# DiscoCarrier.net
KiCad netlist of a schematic drawn in Altium Designer
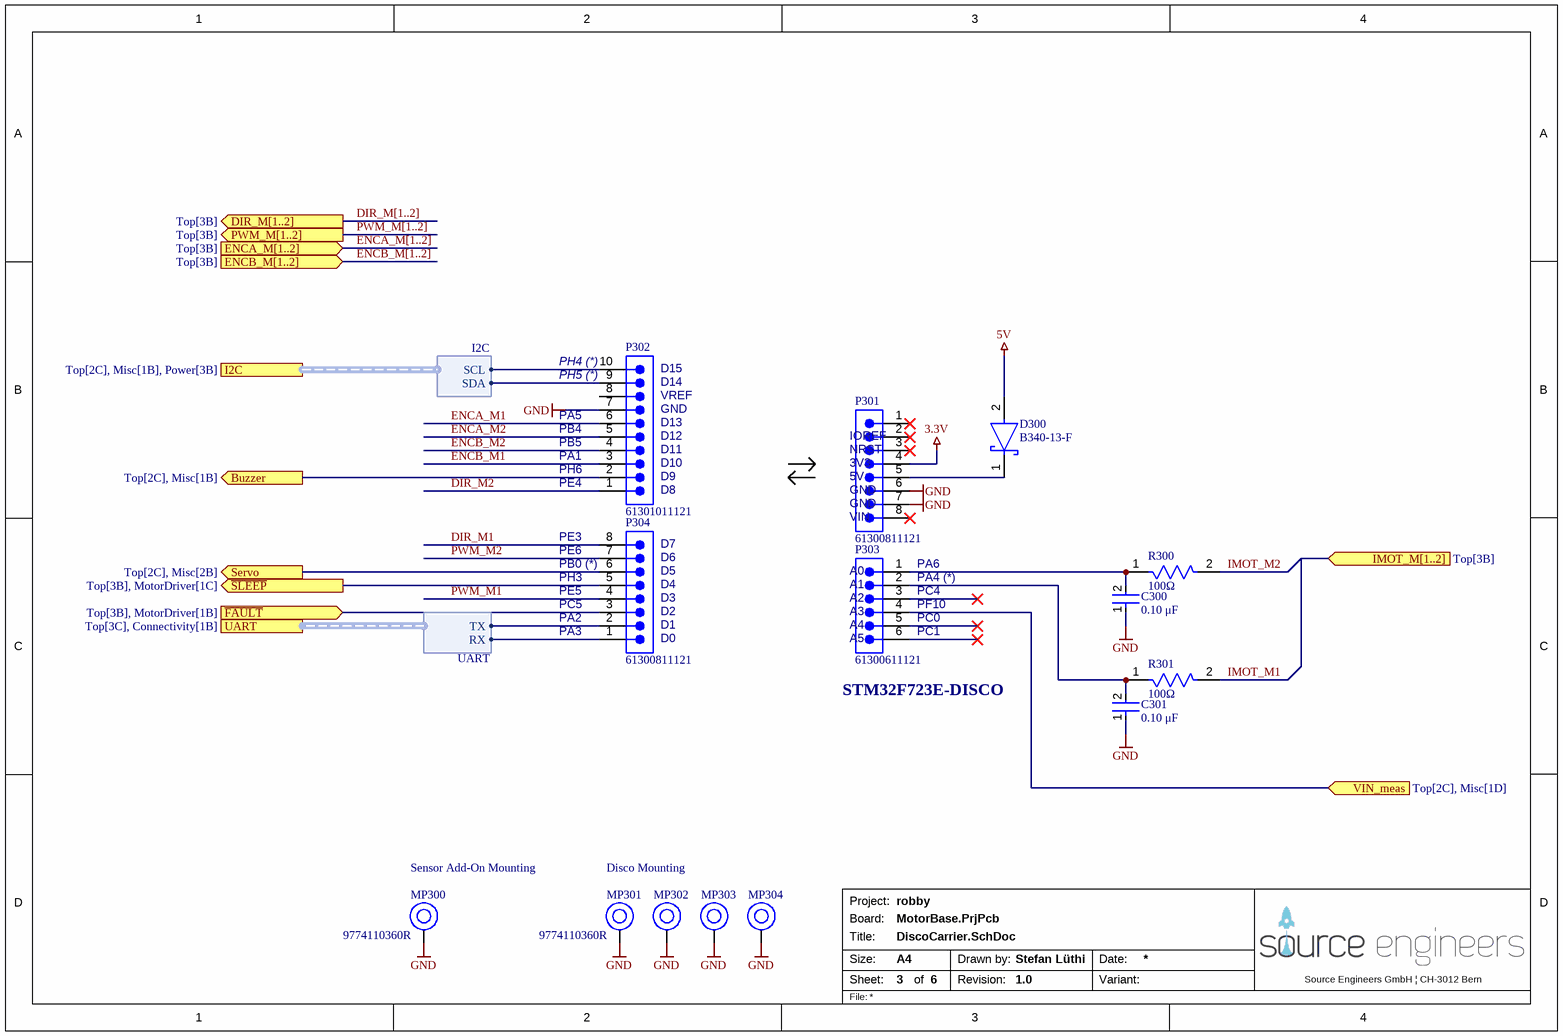
[diagram p0: DiscoCarrier.SchDoc]

(export (version "E")
  (design (tool "Eeschema 10.0.6"))
  (components
    (comp (ref "C300")
      (value "0.10 μF")
      (footprint "FP-C0603C-CF-MFG")
      (description "CAP CER 0.1UF 50V 20% X7R 0603")
      (fields
        (field (name "MANUFACTURER PART NUMBER") "C0603C104M5RACTU")
        (field (name "MANUFACTURER") "KEMET")
      )
      (libsource (lib "Altium Content Vault") (part "b4654b650e69147ec39a6b967a45e02"))
    )
    (comp (ref "C301")
      (value "0.10 μF")
      (footprint "FP-C0603C-CF-MFG")
      (description "CAP CER 0.1UF 50V 20% X7R 0603")
      (fields
        (field (name "MANUFACTURER PART NUMBER") "C0603C104M5RACTU")
        (field (name "MANUFACTURER") "KEMET")
      )
      (libsource (lib "Altium Content Vault") (part "b4654b650e69147ec39a6b967a45e02"))
    )
    (comp (ref "D300")
      (value "B340-13-F")
      (footprint "FP-SMC-MFG")
      (description "DIODE SCHOTTKY 40V 3A SMC")
      (fields
        (field (name "MANUFACTURER") "Diodes Inc.")
        (field (name "OCTOPART") "https://octopart.com/b340-13-f-diodes+inc.-325814")
      )
      (libsource (lib "Altium Content Vault") (part "1d6ec82d83fb6aee721767c19dac4b9"))
    )
    (comp (ref "MP300")
      (value "9774110360R")
      (footprint "9774110360")
      (description "9774110360R Spacer Material: Steel, Tin-Plated Mounting: SMT Series: WA-SMSI Thread D: M3")
      (libsource (lib "Altium Content Vault") (part "Spacer"))
    )
    (comp (ref "MP301")
      (value "9774110360R")
      (footprint "9774110360")
      (description "9774110360R Spacer Material: Steel, Tin-Plated Mounting: SMT Series: WA-SMSI Thread D: M3")
      (libsource (lib "Altium Content Vault") (part "Spacer"))
    )
    (comp (ref "MP302")
      (value "9774110360R")
      (footprint "9774110360")
      (description "9774110360R Spacer Material: Steel, Tin-Plated Mounting: SMT Series: WA-SMSI Thread D: M3")
      (libsource (lib "Altium Content Vault") (part "Spacer"))
    )
    (comp (ref "MP303")
      (value "9774110360R")
      (footprint "9774110360")
      (description "9774110360R Spacer Material: Steel, Tin-Plated Mounting: SMT Series: WA-SMSI Thread D: M3")
      (libsource (lib "Altium Content Vault") (part "Spacer"))
    )
    (comp (ref "MP304")
      (value "9774110360R")
      (footprint "9774110360")
      (description "9774110360R Spacer Material: Steel, Tin-Plated Mounting: SMT Series: WA-SMSI Thread D: M3")
      (libsource (lib "Altium Content Vault") (part "Spacer"))
    )
    (comp (ref "P301")
      (value "61300811121")
      (footprint "61300811121")
      (libsource (lib "Altium Content Vault") (part "Header_Male_1R_08P"))
    )
    (comp (ref "P302")
      (value "61301011121")
      (footprint "61301011121")
      (libsource (lib "Altium Content Vault") (part "Header_Male_1R_10P"))
    )
    (comp (ref "P303")
      (value "61300611121")
      (footprint "61300611121")
      (libsource (lib "Altium Content Vault") (part "Header_Male_1R_06P"))
    )
    (comp (ref "P304")
      (value "61300811121")
      (footprint "61300811121")
      (libsource (lib "Altium Content Vault") (part "Header_Male_1R_08P"))
    )
    (comp (ref "R300")
      (value "RT0603FRE07100RL")
      (footprint "FP-RT0603-MFG")
      (description "RES SMD 100 OHM 1% 1/10W 0603")
      (fields
        (field (name "MANUFACTURER") "Yageo")
        (field (name "RESISTANCE") "100Ω")
        (field (name "TOLERANCE") "0.01")
      )
      (libsource (lib "Altium Content Vault") (part "1029c3af85768c4190bb7ad29bc67b5"))
    )
    (comp (ref "R301")
      (value "RT0603FRE07100RL")
      (footprint "FP-RT0603-MFG")
      (description "RES SMD 100 OHM 1% 1/10W 0603")
      (fields
        (field (name "MANUFACTURER") "Yageo")
        (field (name "RESISTANCE") "100Ω")
        (field (name "TOLERANCE") "0.01")
      )
      (libsource (lib "Altium Content Vault") (part "1029c3af85768c4190bb7ad29bc67b5"))
    )
  )
  (nets
    (net (code "3") (name "/Buzzer") (class "Default")
      (node (ref "P302") (pin "2") (pinfunction "2_2") (pintype "passive"))
    )
    (net (code "4") (name "/DIR_M1") (class "Default")
      (node (ref "P304") (pin "8") (pinfunction "8_8") (pintype "passive"))
    )
    (net (code "5") (name "/DIR_M2") (class "Default")
      (node (ref "P302") (pin "1") (pinfunction "1_1") (pintype "passive"))
    )
    (net (code "7") (name "/ENCA_M1") (class "Default")
      (node (ref "P302") (pin "6") (pinfunction "6_6") (pintype "passive"))
    )
    (net (code "8") (name "/ENCA_M2") (class "Default")
      (node (ref "P302") (pin "5") (pinfunction "5_5") (pintype "passive"))
    )
    (net (code "10") (name "/ENCB_M1") (class "Default")
      (node (ref "P302") (pin "3") (pinfunction "3_3") (pintype "passive"))
    )
    (net (code "11") (name "/ENCB_M2") (class "Default")
      (node (ref "P302") (pin "4") (pinfunction "4_4") (pintype "passive"))
    )
    (net (code "13") (name "/IMOT_M1") (class "Default")
      (node (ref "R301") (pin "2") (pinfunction "2_2") (pintype "passive"))
    )
    (net (code "14") (name "/IMOT_M2") (class "Default")
      (node (ref "R300") (pin "2") (pinfunction "2_2") (pintype "passive"))
    )
    (net (code "16") (name "/PWM_M1") (class "Default")
      (node (ref "P304") (pin "4") (pinfunction "4_4") (pintype "passive"))
    )
    (net (code "17") (name "/PWM_M2") (class "Default")
      (node (ref "P304") (pin "7") (pinfunction "7_7") (pintype "passive"))
    )
    (net (code "19") (name "/RX") (class "Default")
      (node (ref "P304") (pin "1") (pinfunction "1_1") (pintype "passive"))
    )
    (net (code "20") (name "/SCL") (class "Default")
      (node (ref "P302") (pin "10") (pinfunction "10_10") (pintype "passive"))
    )
    (net (code "21") (name "/SDA") (class "Default")
      (node (ref "P302") (pin "9") (pinfunction "9_9") (pintype "passive"))
    )
    (net (code "22") (name "/Servo") (class "Default")
      (node (ref "P304") (pin "6") (pinfunction "6_6") (pintype "passive"))
    )
    (net (code "23") (name "/TX") (class "Default")
      (node (ref "P304") (pin "2") (pinfunction "2_2") (pintype "passive"))
    )
    (net (code "24") (name "/VIN_meas") (class "Default")
      (node (ref "P303") (pin "4") (pinfunction "4_4") (pintype "passive"))
    )
    (net (code "27") (name "/~{FAULT}") (class "Default")
      (node (ref "P304") (pin "3") (pinfunction "3_3") (pintype "passive"))
    )
    (net (code "28") (name "/~{SLEEP}") (class "Default")
      (node (ref "P304") (pin "5") (pinfunction "5_5") (pintype "passive"))
    )
    (net (code "29") (name "3.3V") (class "Default")
      (node (ref "P301") (pin "4") (pinfunction "4_4") (pintype "passive"))
    )
    (net (code "30") (name "5V") (class "Default")
      (node (ref "D300") (pin "2") (pinfunction "A_2") (pintype "passive"))
    )
    (net (code "31") (name "GND") (class "Default")
      (node (ref "C300") (pin "1") (pinfunction "1_1") (pintype "passive"))
      (node (ref "C301") (pin "1") (pinfunction "1_1") (pintype "passive"))
      (node (ref "MP300") (pin "1") (pinfunction "1_1") (pintype "passive"))
      (node (ref "MP301") (pin "1") (pinfunction "1_1") (pintype "passive"))
      (node (ref "MP302") (pin "1") (pinfunction "1_1") (pintype "passive"))
      (node (ref "MP303") (pin "1") (pinfunction "1_1") (pintype "passive"))
      (node (ref "MP304") (pin "1") (pinfunction "1_1") (pintype "passive"))
      (node (ref "P301") (pin "6") (pinfunction "6_6") (pintype "passive"))
      (node (ref "P301") (pin "7") (pinfunction "7_7") (pintype "passive"))
      (node (ref "P302") (pin "7") (pinfunction "7_7") (pintype "passive"))
    )
    (net (code "32") (name "Net-(C300-Pad2)") (class "Default")
      (node (ref "C300") (pin "2") (pinfunction "2_2") (pintype "passive"))
      (node (ref "P303") (pin "1") (pinfunction "1_1") (pintype "passive"))
      (node (ref "R300") (pin "1") (pinfunction "1_1") (pintype "passive"))
    )
    (net (code "33") (name "Net-(C301-Pad2)") (class "Default")
      (node (ref "C301") (pin "2") (pinfunction "2_2") (pintype "passive"))
      (node (ref "P303") (pin "2") (pinfunction "2_2") (pintype "passive"))
      (node (ref "R301") (pin "1") (pinfunction "1_1") (pintype "passive"))
    )
    (net (code "34") (name "Net-(D300-C)") (class "Default")
      (node (ref "D300") (pin "1") (pinfunction "C_1") (pintype "passive"))
      (node (ref "P301") (pin "5") (pinfunction "5_5") (pintype "passive"))
    )
    (net (code "35") (name "unconnected-(P301-Pad1)") (class "Default")
      (node (ref "P301") (pin "1") (pinfunction "1_1") (pintype "passive+no_connect"))
    )
    (net (code "36") (name "unconnected-(P301-Pad2)") (class "Default")
      (node (ref "P301") (pin "2") (pinfunction "2_2") (pintype "passive+no_connect"))
    )
    (net (code "37") (name "unconnected-(P301-Pad3)") (class "Default")
      (node (ref "P301") (pin "3") (pinfunction "3_3") (pintype "passive+no_connect"))
    )
    (net (code "38") (name "unconnected-(P301-Pad8)") (class "Default")
      (node (ref "P301") (pin "8") (pinfunction "8_8") (pintype "passive+no_connect"))
    )
    (net (code "39") (name "unconnected-(P302-Pad8)") (class "Default")
      (node (ref "P302") (pin "8") (pinfunction "8_8") (pintype "passive"))
    )
    (net (code "40") (name "unconnected-(P303-Pad3)") (class "Default")
      (node (ref "P303") (pin "3") (pinfunction "3_3") (pintype "passive+no_connect"))
    )
    (net (code "41") (name "unconnected-(P303-Pad5)") (class "Default")
      (node (ref "P303") (pin "5") (pinfunction "5_5") (pintype "passive+no_connect"))
    )
    (net (code "42") (name "unconnected-(P303-Pad6)") (class "Default")
      (node (ref "P303") (pin "6") (pinfunction "6_6") (pintype "passive+no_connect"))
    )
  )
)
